# Servo_V1_0.net
KiCad netlist of a schematic drawn in EAGLE
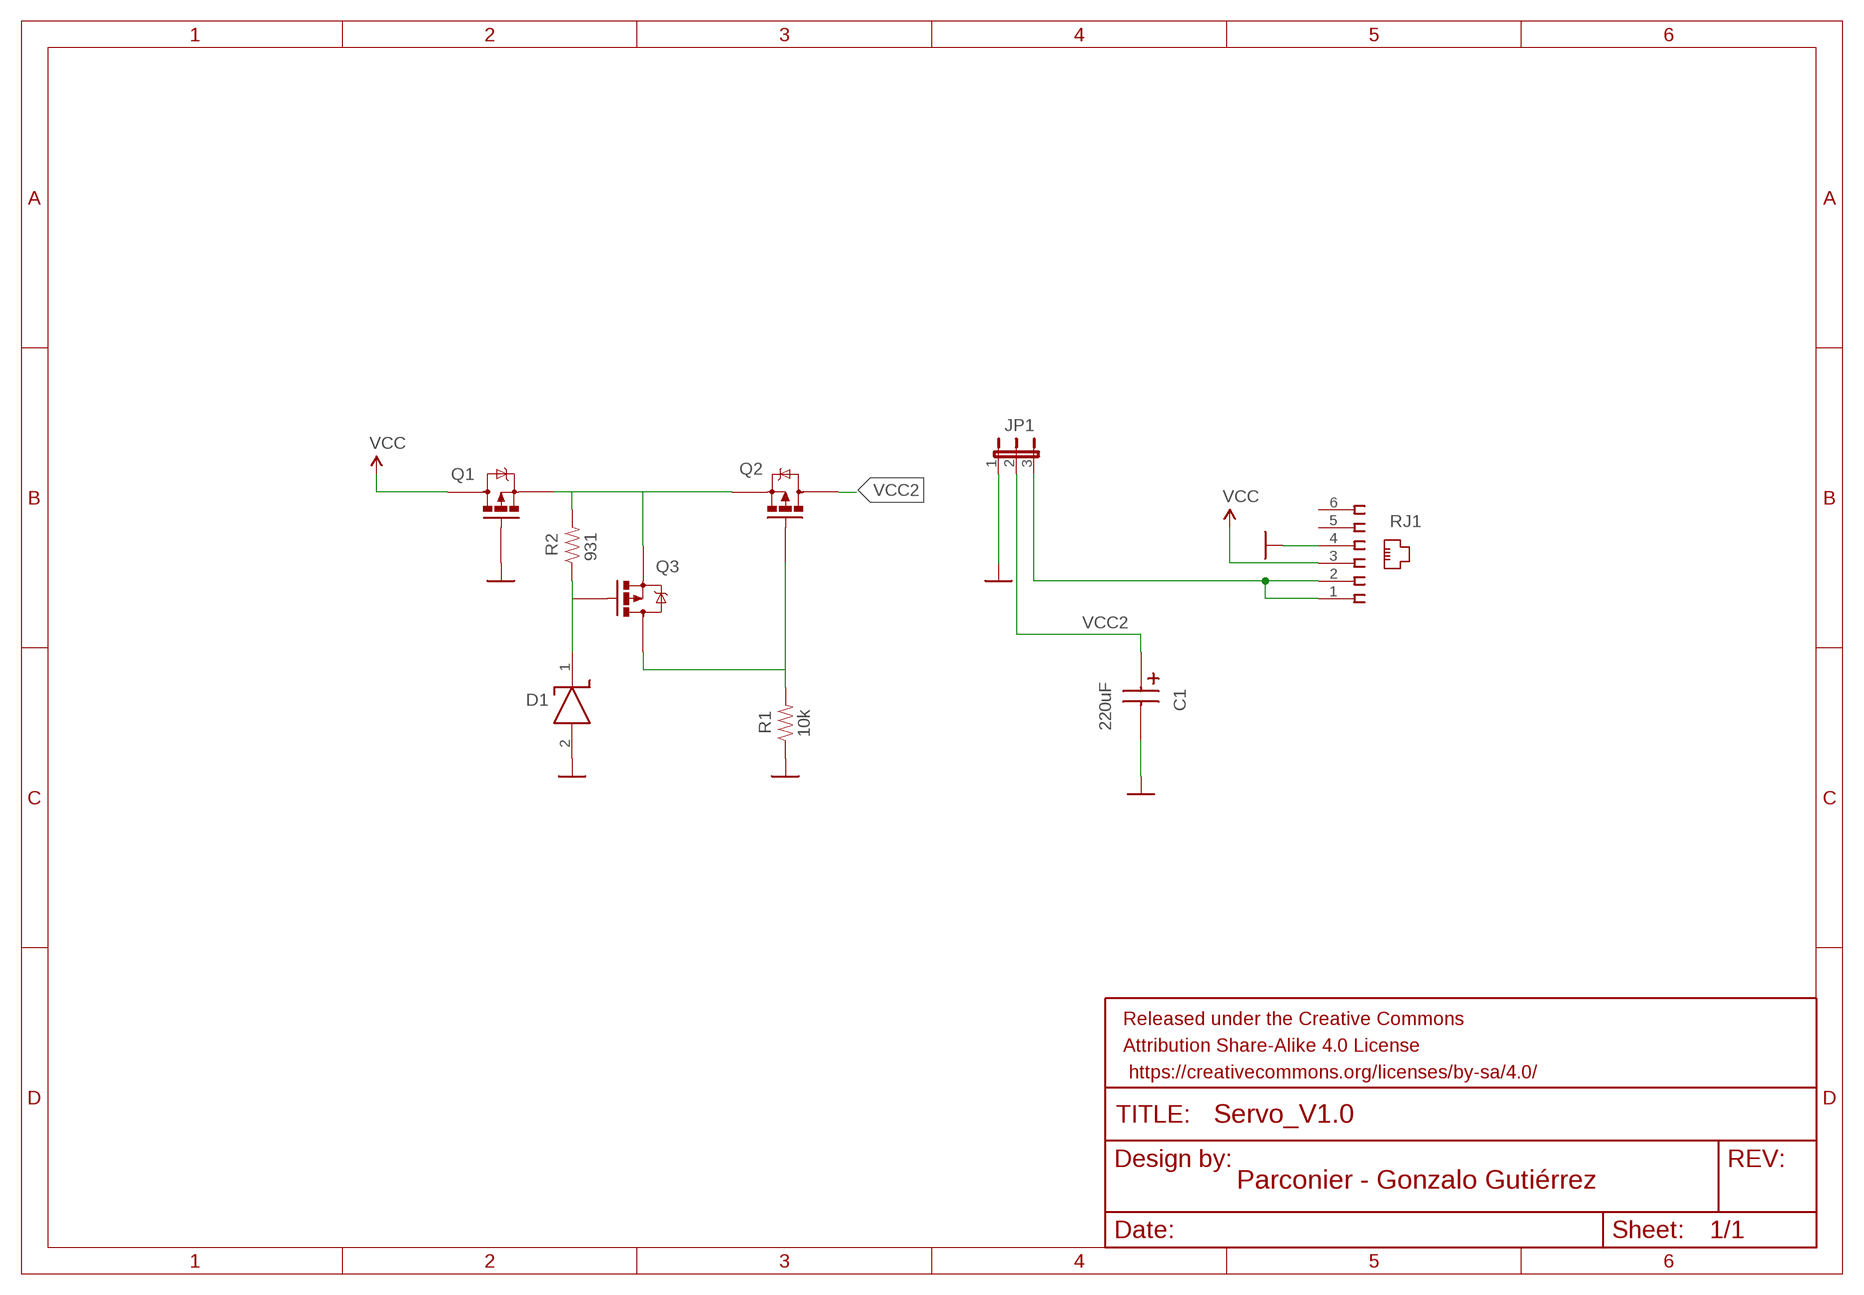
[diagram p0: schematic, sheet 1]

(export (version "E")
  (design (tool "Eeschema 10.0.6"))
  (components
    (comp (ref "C1")
      (value "220uF")
      (footprint "eagle-import:CAPPRD200W80D500H1100")
      (fields (field (name "MANUFACTURER_PART_NUMBER") "860010372006") (field (name "MPN") "227CKS010M"))
      (libsource (lib "eagle-import") (part "860010372006"))
    )
    (comp (ref "D1")
      (value "BZT52C5V1-7-F")
      (footprint "eagle-import:SOD3716X145N")
      (fields (field (name "RS_PART_NUMBER") "7384951P"))
      (libsource (lib "eagle-import") (part "BZT52C5V1-7-F"))
    )
    (comp (ref "JP1")
      (value "JP2E")
      (footprint "eagle-import:JP2")
      (fields (field (name "MPN") "5-146284-3") (field (name "SPICEPREFIX") "J"))
      (libsource (lib "eagle-import") (part "JP2E"))
    )
    (comp (ref "Q1")
      (value "IRLML2244TRPBF")
      (footprint "eagle-import:SOT95P237X112-3N")
      (description "HEXFET Power MOSFET")
      (fields
        (field (name "ARROW_PART_NUMBER") "IRLML2244TRPBF")
        (field (name "HEIGHT") "mm")
        (field (name "MANUFACTURER_NAME") "International Rectifier")
        (field (name "MANUFACTURER_PART_NUMBER") "IRLML2244TRPBF")
      )
      (libsource (lib "eagle-import") (part "IRLML2244TRPBF"))
    )
    (comp (ref "Q2")
      (value "IRLML2244TRPBF")
      (footprint "eagle-import:SOT95P237X112-3N")
      (description "HEXFET Power MOSFET")
      (fields
        (field (name "ARROW_PART_NUMBER") "IRLML2244TRPBF")
        (field (name "HEIGHT") "mm")
        (field (name "MANUFACTURER_NAME") "International Rectifier")
        (field (name "MANUFACTURER_PART_NUMBER") "IRLML2244TRPBF")
      )
      (libsource (lib "eagle-import") (part "IRLML2244TRPBF"))
    )
    (comp (ref "Q3")
      (value "IRLML2244TRPBF")
      (footprint "eagle-import:SOT95P237X112-3N")
      (description "HEXFET Power MOSFET")
      (fields
        (field (name "ARROW_PART_NUMBER") "IRLML2244TRPBF")
        (field (name "HEIGHT") "mm")
        (field (name "MANUFACTURER_NAME") "International Rectifier")
        (field (name "MANUFACTURER_PART_NUMBER") "IRLML2244TRPBF")
      )
      (libsource (lib "eagle-import") (part "IRLML2244TRPBF"))
    )
    (comp (ref "R1")
      (value "10k")
      (footprint "eagle-import:RESC1005X35")
      (fields (field (name "MPN") "RC0402JR-7W10KL"))
      (libsource (lib "eagle-import") (part "RES_0402"))
    )
    (comp (ref "R2")
      (value "931")
      (footprint "eagle-import:RESC1005X35")
      (fields (field (name "MPN") "RC0402FR-07931RL"))
      (libsource (lib "eagle-import") (part "RES_0402"))
    )
    (comp (ref "RJ1")
      (value "615006138421")
      (footprint "eagle-import:615006138421")
      (fields (field (name "RS_PART_NUMBER") "7350282"))
      (libsource (lib "eagle-import") (part "615006138421"))
    )
  )
  (nets
    (net (code "1") (name "GND") (class "Default")
      (node (ref "C1") (pin "2") (pinfunction "-_2") (pintype "bidirectional"))
      (node (ref "D1") (pin "2") (pinfunction "A_2") (pintype "bidirectional"))
      (node (ref "JP1") (pin "1") (pinfunction "1_1") (pintype "passive"))
      (node (ref "Q1") (pin "1") (pinfunction "G_1") (pintype "bidirectional"))
      (node (ref "R1") (pin "1") (pinfunction "1_1") (pintype "passive"))
      (node (ref "RJ1") (pin "4") (pinfunction "4_4") (pintype "input"))
    )
    (net (code "2") (name "Net-(D1-K)") (class "Default")
      (node (ref "D1") (pin "1") (pinfunction "K_1") (pintype "bidirectional"))
      (node (ref "Q3") (pin "1") (pinfunction "G_1") (pintype "bidirectional"))
      (node (ref "R2") (pin "1") (pinfunction "1_1") (pintype "passive"))
    )
    (net (code "3") (name "Net-(JP1-Pad3)") (class "Default")
      (node (ref "JP1") (pin "3") (pinfunction "3_3") (pintype "passive"))
      (node (ref "RJ1") (pin "1") (pinfunction "1_1") (pintype "input"))
      (node (ref "RJ1") (pin "2") (pinfunction "2_2") (pintype "input"))
    )
    (net (code "4") (name "Net-(Q1-S)") (class "Default")
      (node (ref "Q1") (pin "2") (pinfunction "S_2") (pintype "bidirectional"))
      (node (ref "Q2") (pin "2") (pinfunction "S_2") (pintype "bidirectional"))
      (node (ref "Q3") (pin "2") (pinfunction "S_2") (pintype "bidirectional"))
      (node (ref "R2") (pin "2") (pinfunction "2_2") (pintype "passive"))
    )
    (net (code "5") (name "Net-(Q2-G)") (class "Default")
      (node (ref "Q2") (pin "1") (pinfunction "G_1") (pintype "bidirectional"))
      (node (ref "Q3") (pin "3") (pinfunction "D_3") (pintype "bidirectional"))
      (node (ref "R1") (pin "2") (pinfunction "2_2") (pintype "passive"))
    )
    (net (code "6") (name "VCC") (class "Default")
      (node (ref "Q1") (pin "3") (pinfunction "D_3") (pintype "bidirectional"))
      (node (ref "RJ1") (pin "3") (pinfunction "3_3") (pintype "input"))
    )
    (net (code "7") (name "VCC2") (class "Default")
      (node (ref "C1") (pin "1") (pinfunction "+_1") (pintype "bidirectional"))
      (node (ref "JP1") (pin "2") (pinfunction "2_2") (pintype "passive"))
      (node (ref "Q2") (pin "3") (pinfunction "D_3") (pintype "bidirectional"))
    )
    (net (code "8") (name "unconnected-(RJ1-Pad5)") (class "Default")
      (node (ref "RJ1") (pin "5") (pinfunction "5_5") (pintype "input"))
    )
    (net (code "9") (name "unconnected-(RJ1-Pad6)") (class "Default")
      (node (ref "RJ1") (pin "6") (pinfunction "6_6") (pintype "input"))
    )
  )
)
